# CANBUS_USB.net
KiCad netlist of a schematic drawn in EAGLE
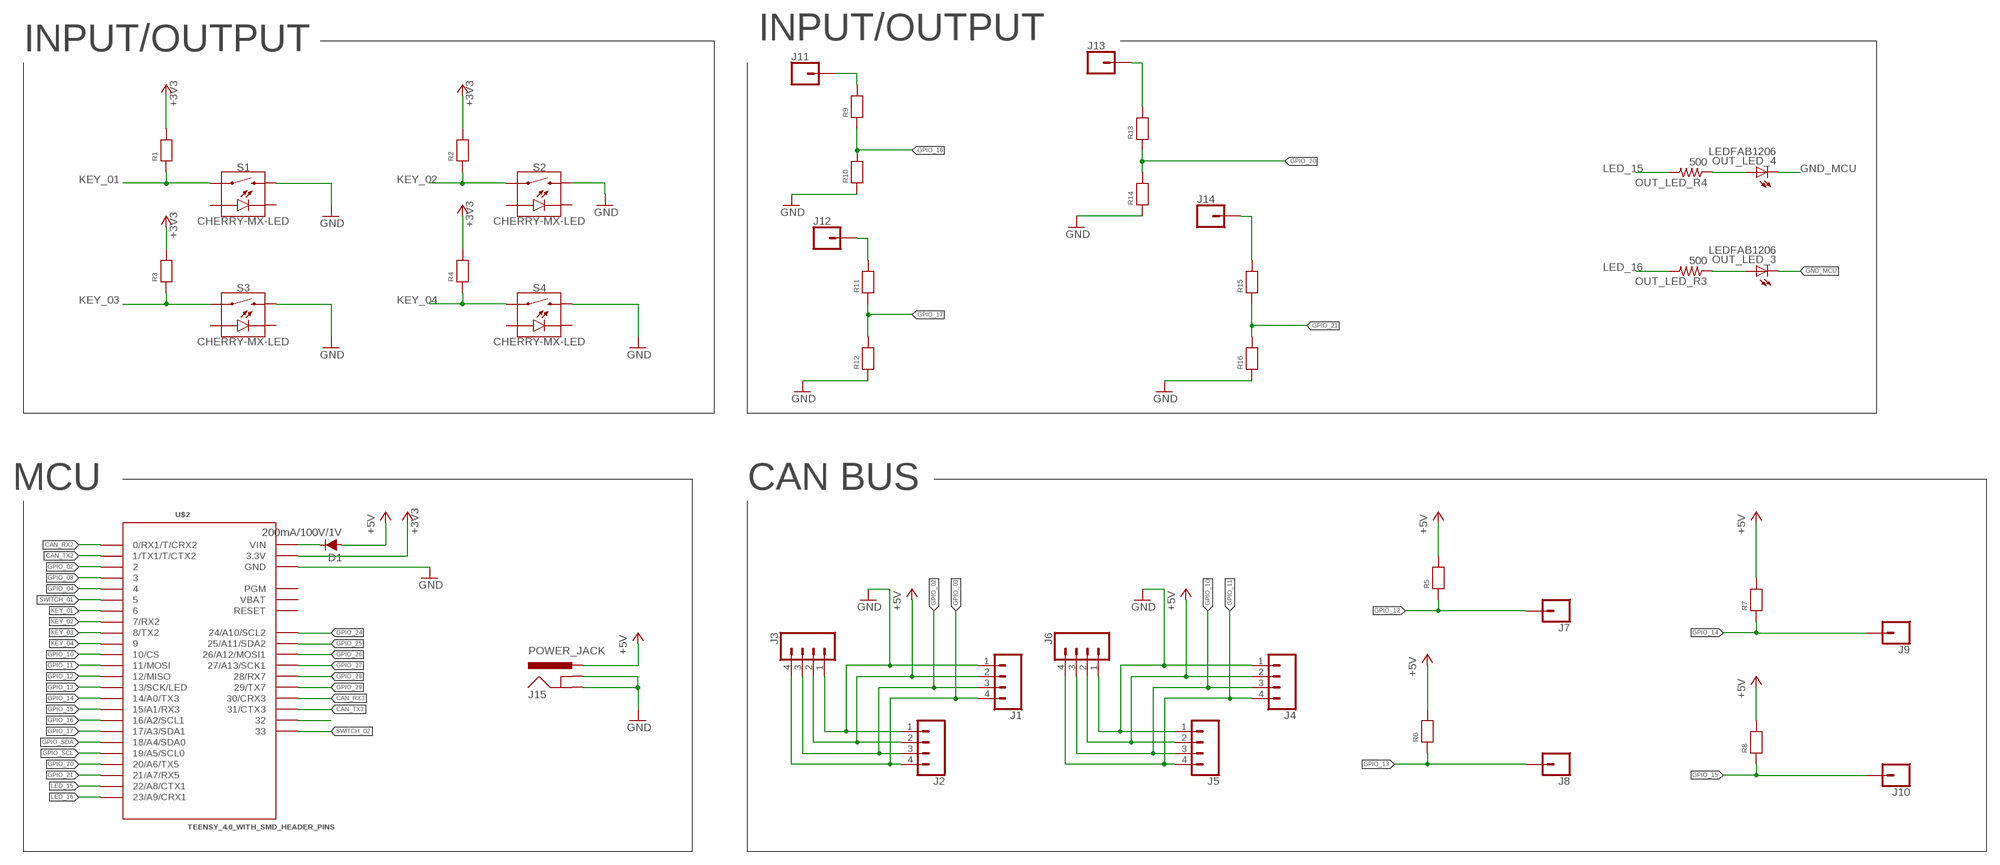
[diagram p0: schematic, sheet 1]

(export (version "E")
  (design (tool "Eeschema 10.0.6"))
  (components
    (comp (ref "D1")
      (value "200mA/100V/1V")
      (footprint "eagle-import:DIODE-1N4148")
      (libsource (lib "eagle-import") (part "DIODE-1N4148"))
    )
    (comp (ref "J1")
      (value "CONN_04")
      (footprint "eagle-import:1X04")
      (libsource (lib "eagle-import") (part "CONN_04"))
    )
    (comp (ref "J2")
      (value "CONN_04")
      (footprint "eagle-import:1X04")
      (libsource (lib "eagle-import") (part "CONN_04"))
    )
    (comp (ref "J3")
      (value "CONN_04")
      (footprint "eagle-import:1X04")
      (libsource (lib "eagle-import") (part "CONN_04"))
    )
    (comp (ref "J4")
      (value "CONN_04")
      (footprint "eagle-import:1X04")
      (libsource (lib "eagle-import") (part "CONN_04"))
    )
    (comp (ref "J5")
      (value "CONN_04")
      (footprint "eagle-import:1X04")
      (libsource (lib "eagle-import") (part "CONN_04"))
    )
    (comp (ref "J6")
      (value "CONN_04")
      (footprint "eagle-import:1X04")
      (libsource (lib "eagle-import") (part "CONN_04"))
    )
    (comp (ref "J7")
      (value "CONN_01")
      (footprint "eagle-import:1X01")
      (libsource (lib "eagle-import") (part "CONN_01"))
    )
    (comp (ref "J8")
      (value "CONN_01")
      (footprint "eagle-import:1X01")
      (libsource (lib "eagle-import") (part "CONN_01"))
    )
    (comp (ref "J9")
      (value "CONN_01")
      (footprint "eagle-import:1X01")
      (libsource (lib "eagle-import") (part "CONN_01"))
    )
    (comp (ref "J10")
      (value "CONN_01")
      (footprint "eagle-import:1X01")
      (libsource (lib "eagle-import") (part "CONN_01"))
    )
    (comp (ref "J11")
      (value "CONN_01")
      (footprint "eagle-import:1X01")
      (libsource (lib "eagle-import") (part "CONN_01"))
    )
    (comp (ref "J12")
      (value "CONN_01")
      (footprint "eagle-import:1X01")
      (libsource (lib "eagle-import") (part "CONN_01"))
    )
    (comp (ref "J13")
      (value "CONN_01")
      (footprint "eagle-import:1X01")
      (libsource (lib "eagle-import") (part "CONN_01"))
    )
    (comp (ref "J14")
      (value "CONN_01")
      (footprint "eagle-import:1X01")
      (libsource (lib "eagle-import") (part "CONN_01"))
    )
    (comp (ref "J15")
      (value "POWER_JACK")
      (footprint "eagle-import:POWER_JACK_PTH")
      (libsource (lib "eagle-import") (part "POWER_JACK"))
    )
    (comp (ref "OUT_LED_3")
      (value "LEDFAB1206")
      (footprint "eagle-import:LED1206FAB")
      (libsource (lib "eagle-import") (part "LEDFAB1206"))
    )
    (comp (ref "OUT_LED_4")
      (value "LEDFAB1206")
      (footprint "eagle-import:LED1206FAB")
      (libsource (lib "eagle-import") (part "LEDFAB1206"))
    )
    (comp (ref "OUT_LED_R3")
      (value "500")
      (footprint "eagle-import:R1206FAB")
      (libsource (lib "eagle-import") (part "RES-US1206FAB"))
    )
    (comp (ref "OUT_LED_R4")
      (value "500")
      (footprint "eagle-import:R1206FAB")
      (libsource (lib "eagle-import") (part "RES-US1206FAB"))
    )
    (comp (ref "R1")
      (value "RESISTOR1206")
      (footprint "eagle-import:1206")
      (libsource (lib "eagle-import") (part "RESISTOR1206"))
    )
    (comp (ref "R2")
      (value "RESISTOR1206")
      (footprint "eagle-import:1206")
      (libsource (lib "eagle-import") (part "RESISTOR1206"))
    )
    (comp (ref "R3")
      (value "RESISTOR1206")
      (footprint "eagle-import:1206")
      (libsource (lib "eagle-import") (part "RESISTOR1206"))
    )
    (comp (ref "R4")
      (value "RESISTOR1206")
      (footprint "eagle-import:1206")
      (libsource (lib "eagle-import") (part "RESISTOR1206"))
    )
    (comp (ref "R5")
      (value "RESISTOR1206")
      (footprint "eagle-import:1206")
      (libsource (lib "eagle-import") (part "RESISTOR1206"))
    )
    (comp (ref "R6")
      (value "RESISTOR1206")
      (footprint "eagle-import:1206")
      (libsource (lib "eagle-import") (part "RESISTOR1206"))
    )
    (comp (ref "R7")
      (value "RESISTOR1206")
      (footprint "eagle-import:1206")
      (libsource (lib "eagle-import") (part "RESISTOR1206"))
    )
    (comp (ref "R8")
      (value "RESISTOR1206")
      (footprint "eagle-import:1206")
      (libsource (lib "eagle-import") (part "RESISTOR1206"))
    )
    (comp (ref "R9")
      (value "RESISTOR1206")
      (footprint "eagle-import:1206")
      (libsource (lib "eagle-import") (part "RESISTOR1206"))
    )
    (comp (ref "R10")
      (value "RESISTOR1206")
      (footprint "eagle-import:1206")
      (libsource (lib "eagle-import") (part "RESISTOR1206"))
    )
    (comp (ref "R11")
      (value "RESISTOR1206")
      (footprint "eagle-import:1206")
      (libsource (lib "eagle-import") (part "RESISTOR1206"))
    )
    (comp (ref "R12")
      (value "RESISTOR1206")
      (footprint "eagle-import:1206")
      (libsource (lib "eagle-import") (part "RESISTOR1206"))
    )
    (comp (ref "R13")
      (value "RESISTOR1206")
      (footprint "eagle-import:1206")
      (libsource (lib "eagle-import") (part "RESISTOR1206"))
    )
    (comp (ref "R14")
      (value "RESISTOR1206")
      (footprint "eagle-import:1206")
      (libsource (lib "eagle-import") (part "RESISTOR1206"))
    )
    (comp (ref "R15")
      (value "RESISTOR1206")
      (footprint "eagle-import:1206")
      (libsource (lib "eagle-import") (part "RESISTOR1206"))
    )
    (comp (ref "R16")
      (value "RESISTOR1206")
      (footprint "eagle-import:1206")
      (libsource (lib "eagle-import") (part "RESISTOR1206"))
    )
    (comp (ref "S1")
      (value "CHERRY-MX-LED")
      (footprint "eagle-import:CHERRY-MX-LED")
      (libsource (lib "eagle-import") (part "CHERRY-MX-LED"))
    )
    (comp (ref "S2")
      (value "CHERRY-MX-LED")
      (footprint "eagle-import:CHERRY-MX-LED")
      (libsource (lib "eagle-import") (part "CHERRY-MX-LED"))
    )
    (comp (ref "S3")
      (value "CHERRY-MX-LED")
      (footprint "eagle-import:CHERRY-MX-LED")
      (libsource (lib "eagle-import") (part "CHERRY-MX-LED"))
    )
    (comp (ref "S4")
      (value "CHERRY-MX-LED")
      (footprint "eagle-import:CHERRY-MX-LED")
      (libsource (lib "eagle-import") (part "CHERRY-MX-LED"))
    )
    (comp (ref "U$2")
      (value "TEENSY_4.0_WITH_SMD_HEADER_PINS")
      (footprint "eagle-import:TEENSY_4.0_WITH_SMD_HEADER_PINS")
      (libsource (lib "eagle-import") (part "TEENSY_4.0_WITH_SMD_HEADER_PINS"))
    )
  )
  (nets
    (net (code "1") (name "+3V3") (class "Default")
      (node (ref "R1") (pin "2") (pinfunction "2_2") (pintype "passive"))
      (node (ref "R2") (pin "2") (pinfunction "2_2") (pintype "passive"))
      (node (ref "R3") (pin "2") (pinfunction "2_2") (pintype "passive"))
      (node (ref "R4") (pin "2") (pinfunction "2_2") (pintype "passive"))
      (node (ref "U$2") (pin "3.3V") (pinfunction "3.3V_3.3V") (pintype "power_in"))
      (node (ref "U$2") (pin "3.3V1") (pinfunction "3.3V_3.3V1") (pintype "power_in"))
    )
    (net (code "2") (name "+5V") (class "Default")
      (node (ref "D1") (pin "A") (pinfunction "A_A") (pintype "passive"))
      (node (ref "J1") (pin "2") (pinfunction "2_2") (pintype "passive"))
      (node (ref "J15") (pin "PWR") (pinfunction "PWR_PWR") (pintype "bidirectional"))
      (node (ref "J2") (pin "2") (pinfunction "2_2") (pintype "passive"))
      (node (ref "J3") (pin "2") (pinfunction "2_2") (pintype "passive"))
      (node (ref "J4") (pin "2") (pinfunction "2_2") (pintype "passive"))
      (node (ref "J5") (pin "2") (pinfunction "2_2") (pintype "passive"))
      (node (ref "J6") (pin "2") (pinfunction "2_2") (pintype "passive"))
      (node (ref "R5") (pin "2") (pinfunction "2_2") (pintype "passive"))
      (node (ref "R6") (pin "2") (pinfunction "2_2") (pintype "passive"))
      (node (ref "R7") (pin "2") (pinfunction "2_2") (pintype "passive"))
      (node (ref "R8") (pin "2") (pinfunction "2_2") (pintype "passive"))
    )
    (net (code "3") (name "/VBAT") (class "Default")
      (node (ref "U$2") (pin "VBAT") (pinfunction "VBAT_VBAT") (pintype "power_in"))
    )
    (net (code "4") (name "CAN_RX2") (class "Default")
      (node (ref "U$2") (pin "0") (pinfunction "0/RX1/T/CRX2_0") (pintype "bidirectional"))
    )
    (net (code "5") (name "CAN_RX3") (class "Default")
      (node (ref "U$2") (pin "30") (pinfunction "30/CRX3_30") (pintype "bidirectional"))
    )
    (net (code "6") (name "CAN_TX2") (class "Default")
      (node (ref "U$2") (pin "1") (pinfunction "1/TX1/T/CTX2_1") (pintype "bidirectional"))
    )
    (net (code "7") (name "CAN_TX3") (class "Default")
      (node (ref "U$2") (pin "31") (pinfunction "31/CTX3_31") (pintype "bidirectional"))
    )
    (net (code "8") (name "GND") (class "Default")
      (node (ref "J1") (pin "1") (pinfunction "1_1") (pintype "passive"))
      (node (ref "J15") (pin "GND") (pinfunction "GND_GND") (pintype "bidirectional"))
      (node (ref "J15") (pin "GNDBREAK") (pinfunction "GNDBREAK_GNDBREAK") (pintype "bidirectional"))
      (node (ref "J2") (pin "1") (pinfunction "1_1") (pintype "passive"))
      (node (ref "J3") (pin "1") (pinfunction "1_1") (pintype "passive"))
      (node (ref "J4") (pin "1") (pinfunction "1_1") (pintype "passive"))
      (node (ref "J5") (pin "1") (pinfunction "1_1") (pintype "passive"))
      (node (ref "J6") (pin "1") (pinfunction "1_1") (pintype "passive"))
      (node (ref "R10") (pin "1") (pinfunction "1_1") (pintype "passive"))
      (node (ref "R12") (pin "1") (pinfunction "1_1") (pintype "passive"))
      (node (ref "R14") (pin "1") (pinfunction "1_1") (pintype "passive"))
      (node (ref "R16") (pin "1") (pinfunction "1_1") (pintype "passive"))
      (node (ref "S1") (pin "S2") (pinfunction "S2_S2") (pintype "passive"))
      (node (ref "S2") (pin "S2") (pinfunction "S2_S2") (pintype "passive"))
      (node (ref "S3") (pin "S2") (pinfunction "S2_S2") (pintype "passive"))
      (node (ref "S4") (pin "S2") (pinfunction "S2_S2") (pintype "passive"))
      (node (ref "U$2") (pin "GND") (pinfunction "GND_GND") (pintype "power_in"))
      (node (ref "U$2") (pin "GND1") (pinfunction "GND_GND1") (pintype "power_in"))
      (node (ref "U$2") (pin "GND2") (pinfunction "GND_GND2") (pintype "power_in"))
    )
    (net (code "9") (name "GND_MCU") (class "Default")
      (node (ref "OUT_LED_3") (pin "2") (pinfunction "C_2") (pintype "passive"))
      (node (ref "OUT_LED_4") (pin "2") (pinfunction "C_2") (pintype "passive"))
    )
    (net (code "10") (name "GPIO_02") (class "Default")
      (node (ref "J1") (pin "3") (pinfunction "3_3") (pintype "passive"))
      (node (ref "J2") (pin "3") (pinfunction "3_3") (pintype "passive"))
      (node (ref "J3") (pin "3") (pinfunction "3_3") (pintype "passive"))
      (node (ref "U$2") (pin "2") (pinfunction "2_2") (pintype "bidirectional"))
    )
    (net (code "11") (name "GPIO_03") (class "Default")
      (node (ref "J1") (pin "4") (pinfunction "4_4") (pintype "passive"))
      (node (ref "J2") (pin "4") (pinfunction "4_4") (pintype "passive"))
      (node (ref "J3") (pin "4") (pinfunction "4_4") (pintype "passive"))
      (node (ref "U$2") (pin "3") (pinfunction "3_3") (pintype "bidirectional"))
    )
    (net (code "12") (name "GPIO_04") (class "Default")
      (node (ref "U$2") (pin "4") (pinfunction "4_4") (pintype "bidirectional"))
    )
    (net (code "13") (name "GPIO_10") (class "Default")
      (node (ref "J4") (pin "3") (pinfunction "3_3") (pintype "passive"))
      (node (ref "J5") (pin "3") (pinfunction "3_3") (pintype "passive"))
      (node (ref "J6") (pin "3") (pinfunction "3_3") (pintype "passive"))
      (node (ref "U$2") (pin "10") (pinfunction "10/CS_10") (pintype "bidirectional"))
    )
    (net (code "14") (name "GPIO_11") (class "Default")
      (node (ref "J4") (pin "4") (pinfunction "4_4") (pintype "passive"))
      (node (ref "J5") (pin "4") (pinfunction "4_4") (pintype "passive"))
      (node (ref "J6") (pin "4") (pinfunction "4_4") (pintype "passive"))
      (node (ref "U$2") (pin "11") (pinfunction "11/MOSI_11") (pintype "bidirectional"))
    )
    (net (code "15") (name "GPIO_12") (class "Default")
      (node (ref "J7") (pin "1") (pinfunction "1_1") (pintype "passive"))
      (node (ref "R5") (pin "1") (pinfunction "1_1") (pintype "passive"))
      (node (ref "U$2") (pin "12") (pinfunction "12/MISO_12") (pintype "bidirectional"))
    )
    (net (code "16") (name "GPIO_13") (class "Default")
      (node (ref "J8") (pin "1") (pinfunction "1_1") (pintype "passive"))
      (node (ref "R6") (pin "1") (pinfunction "1_1") (pintype "passive"))
      (node (ref "U$2") (pin "13") (pinfunction "13/SCK/LED_13") (pintype "bidirectional"))
    )
    (net (code "17") (name "GPIO_14") (class "Default")
      (node (ref "J9") (pin "1") (pinfunction "1_1") (pintype "passive"))
      (node (ref "R7") (pin "1") (pinfunction "1_1") (pintype "passive"))
      (node (ref "U$2") (pin "14/A0") (pinfunction "14/A0/TX3_14/A0") (pintype "bidirectional"))
    )
    (net (code "18") (name "GPIO_15") (class "Default")
      (node (ref "J10") (pin "1") (pinfunction "1_1") (pintype "passive"))
      (node (ref "R8") (pin "1") (pinfunction "1_1") (pintype "passive"))
      (node (ref "U$2") (pin "15/A1") (pinfunction "15/A1/RX3_15/A1") (pintype "bidirectional"))
    )
    (net (code "19") (name "GPIO_16") (class "Default")
      (node (ref "R10") (pin "2") (pinfunction "2_2") (pintype "passive"))
      (node (ref "R9") (pin "1") (pinfunction "1_1") (pintype "passive"))
      (node (ref "U$2") (pin "16/A2") (pinfunction "16/A2/SCL1_16/A2") (pintype "bidirectional"))
    )
    (net (code "20") (name "GPIO_17") (class "Default")
      (node (ref "R11") (pin "1") (pinfunction "1_1") (pintype "passive"))
      (node (ref "R12") (pin "2") (pinfunction "2_2") (pintype "passive"))
      (node (ref "U$2") (pin "17/A3") (pinfunction "17/A3/SDA1_17/A3") (pintype "bidirectional"))
    )
    (net (code "21") (name "GPIO_20") (class "Default")
      (node (ref "R13") (pin "1") (pinfunction "1_1") (pintype "passive"))
      (node (ref "R14") (pin "2") (pinfunction "2_2") (pintype "passive"))
      (node (ref "U$2") (pin "20/A6") (pinfunction "20/A6/TX5_20/A6") (pintype "bidirectional"))
    )
    (net (code "22") (name "GPIO_21") (class "Default")
      (node (ref "R15") (pin "1") (pinfunction "1_1") (pintype "passive"))
      (node (ref "R16") (pin "2") (pinfunction "2_2") (pintype "passive"))
      (node (ref "U$2") (pin "21/A7") (pinfunction "21/A7/RX5_21/A7") (pintype "bidirectional"))
    )
    (net (code "23") (name "GPIO_24") (class "Default")
      (node (ref "U$2") (pin "24") (pinfunction "24/A10/SCL2_24") (pintype "bidirectional"))
    )
    (net (code "24") (name "GPIO_25") (class "Default")
      (node (ref "U$2") (pin "25") (pinfunction "25/A11/SDA2_25") (pintype "bidirectional"))
    )
    (net (code "25") (name "GPIO_26") (class "Default")
      (node (ref "U$2") (pin "26") (pinfunction "26/A12/MOSI1_26") (pintype "bidirectional"))
    )
    (net (code "26") (name "GPIO_27") (class "Default")
      (node (ref "U$2") (pin "27") (pinfunction "27/A13/SCK1_27") (pintype "bidirectional"))
    )
    (net (code "27") (name "GPIO_28") (class "Default")
      (node (ref "U$2") (pin "28") (pinfunction "28/RX7_28") (pintype "bidirectional"))
    )
    (net (code "28") (name "GPIO_29") (class "Default")
      (node (ref "U$2") (pin "29") (pinfunction "29/TX7_29") (pintype "bidirectional"))
    )
    (net (code "29") (name "GPIO_SCL") (class "Default")
      (node (ref "U$2") (pin "19/A5") (pinfunction "19/A5/SCL0_19/A5") (pintype "bidirectional"))
    )
    (net (code "30") (name "GPIO_SDA") (class "Default")
      (node (ref "U$2") (pin "18/A4") (pinfunction "18/A4/SDA0_18/A4") (pintype "bidirectional"))
    )
    (net (code "31") (name "KEY_01") (class "Default")
      (node (ref "R1") (pin "1") (pinfunction "1_1") (pintype "passive"))
      (node (ref "S1") (pin "S1") (pinfunction "S1_S1") (pintype "passive"))
      (node (ref "U$2") (pin "6") (pinfunction "6_6") (pintype "bidirectional"))
    )
    (net (code "32") (name "KEY_02") (class "Default")
      (node (ref "R2") (pin "1") (pinfunction "1_1") (pintype "passive"))
      (node (ref "S2") (pin "S1") (pinfunction "S1_S1") (pintype "passive"))
      (node (ref "U$2") (pin "7") (pinfunction "7/RX2_7") (pintype "bidirectional"))
    )
    (net (code "33") (name "KEY_03") (class "Default")
      (node (ref "R3") (pin "1") (pinfunction "1_1") (pintype "passive"))
      (node (ref "S3") (pin "S1") (pinfunction "S1_S1") (pintype "passive"))
      (node (ref "U$2") (pin "8") (pinfunction "8/TX2_8") (pintype "bidirectional"))
    )
    (net (code "34") (name "KEY_04") (class "Default")
      (node (ref "R4") (pin "1") (pinfunction "1_1") (pintype "passive"))
      (node (ref "S4") (pin "S1") (pinfunction "S1_S1") (pintype "passive"))
      (node (ref "U$2") (pin "9") (pinfunction "9_9") (pintype "bidirectional"))
    )
    (net (code "35") (name "LED_15") (class "Default")
      (node (ref "OUT_LED_R4") (pin "2") (pinfunction "2_2") (pintype "passive"))
      (node (ref "U$2") (pin "22/A8") (pinfunction "22/A8/CTX1_22/A8") (pintype "bidirectional"))
    )
    (net (code "36") (name "LED_16") (class "Default")
      (node (ref "OUT_LED_R3") (pin "2") (pinfunction "2_2") (pintype "passive"))
      (node (ref "U$2") (pin "23/A9") (pinfunction "23/A9/CRX1_23/A9") (pintype "bidirectional"))
    )
    (net (code "37") (name "Net-(D1-PadC)") (class "Default")
      (node (ref "D1") (pin "C") (pinfunction "C_C") (pintype "passive"))
      (node (ref "U$2") (pin "VIN") (pinfunction "VIN_VIN") (pintype "power_in"))
    )
    (net (code "38") (name "Net-(J11-Pad1)") (class "Default")
      (node (ref "J11") (pin "1") (pinfunction "1_1") (pintype "passive"))
      (node (ref "R9") (pin "2") (pinfunction "2_2") (pintype "passive"))
    )
    (net (code "39") (name "Net-(J12-Pad1)") (class "Default")
      (node (ref "J12") (pin "1") (pinfunction "1_1") (pintype "passive"))
      (node (ref "R11") (pin "2") (pinfunction "2_2") (pintype "passive"))
    )
    (net (code "40") (name "Net-(J13-Pad1)") (class "Default")
      (node (ref "J13") (pin "1") (pinfunction "1_1") (pintype "passive"))
      (node (ref "R13") (pin "2") (pinfunction "2_2") (pintype "passive"))
    )
    (net (code "41") (name "Net-(J14-Pad1)") (class "Default")
      (node (ref "J14") (pin "1") (pinfunction "1_1") (pintype "passive"))
      (node (ref "R15") (pin "2") (pinfunction "2_2") (pintype "passive"))
    )
    (net (code "42") (name "Net-(OUT_LED_3-A)") (class "Default")
      (node (ref "OUT_LED_3") (pin "1") (pinfunction "A_1") (pintype "passive"))
      (node (ref "OUT_LED_R3") (pin "1") (pinfunction "1_1") (pintype "passive"))
    )
    (net (code "43") (name "Net-(OUT_LED_4-A)") (class "Default")
      (node (ref "OUT_LED_4") (pin "1") (pinfunction "A_1") (pintype "passive"))
      (node (ref "OUT_LED_R4") (pin "1") (pinfunction "1_1") (pintype "passive"))
    )
    (net (code "44") (name "SWITCH_01") (class "Default")
      (node (ref "U$2") (pin "5") (pinfunction "5_5") (pintype "bidirectional"))
    )
    (net (code "45") (name "SWITCH_02") (class "Default")
      (node (ref "U$2") (pin "33") (pinfunction "33_33") (pintype "bidirectional"))
    )
    (net (code "46") (name "unconnected-(S1-C-PadK)") (class "Default")
      (node (ref "S1") (pin "K") (pinfunction "C_K") (pintype "passive"))
    )
    (net (code "47") (name "unconnected-(S1-PadA)") (class "Default")
      (node (ref "S1") (pin "A") (pinfunction "A_A") (pintype "passive"))
    )
    (net (code "48") (name "unconnected-(S2-C-PadK)") (class "Default")
      (node (ref "S2") (pin "K") (pinfunction "C_K") (pintype "passive"))
    )
    (net (code "49") (name "unconnected-(S2-PadA)") (class "Default")
      (node (ref "S2") (pin "A") (pinfunction "A_A") (pintype "passive"))
    )
    (net (code "50") (name "unconnected-(S3-C-PadK)") (class "Default")
      (node (ref "S3") (pin "K") (pinfunction "C_K") (pintype "passive"))
    )
    (net (code "51") (name "unconnected-(S3-PadA)") (class "Default")
      (node (ref "S3") (pin "A") (pinfunction "A_A") (pintype "passive"))
    )
    (net (code "52") (name "unconnected-(S4-C-PadK)") (class "Default")
      (node (ref "S4") (pin "K") (pinfunction "C_K") (pintype "passive"))
    )
    (net (code "53") (name "unconnected-(S4-PadA)") (class "Default")
      (node (ref "S4") (pin "A") (pinfunction "A_A") (pintype "passive"))
    )
    (net (code "54") (name "unconnected-(U$2-Pad32)") (class "Default")
      (node (ref "U$2") (pin "32") (pinfunction "32_32") (pintype "bidirectional"))
    )
    (net (code "55") (name "unconnected-(U$2-PadPGM)") (class "Default")
      (node (ref "U$2") (pin "PGM") (pinfunction "PGM_PGM") (pintype "bidirectional"))
    )
    (net (code "56") (name "unconnected-(U$2-PadRESET)") (class "Default")
      (node (ref "U$2") (pin "RESET") (pinfunction "RESET_RESET") (pintype "bidirectional"))
    )
  )
)
